# H10R4.net
KiCad netlist of a schematic drawn in EAGLE
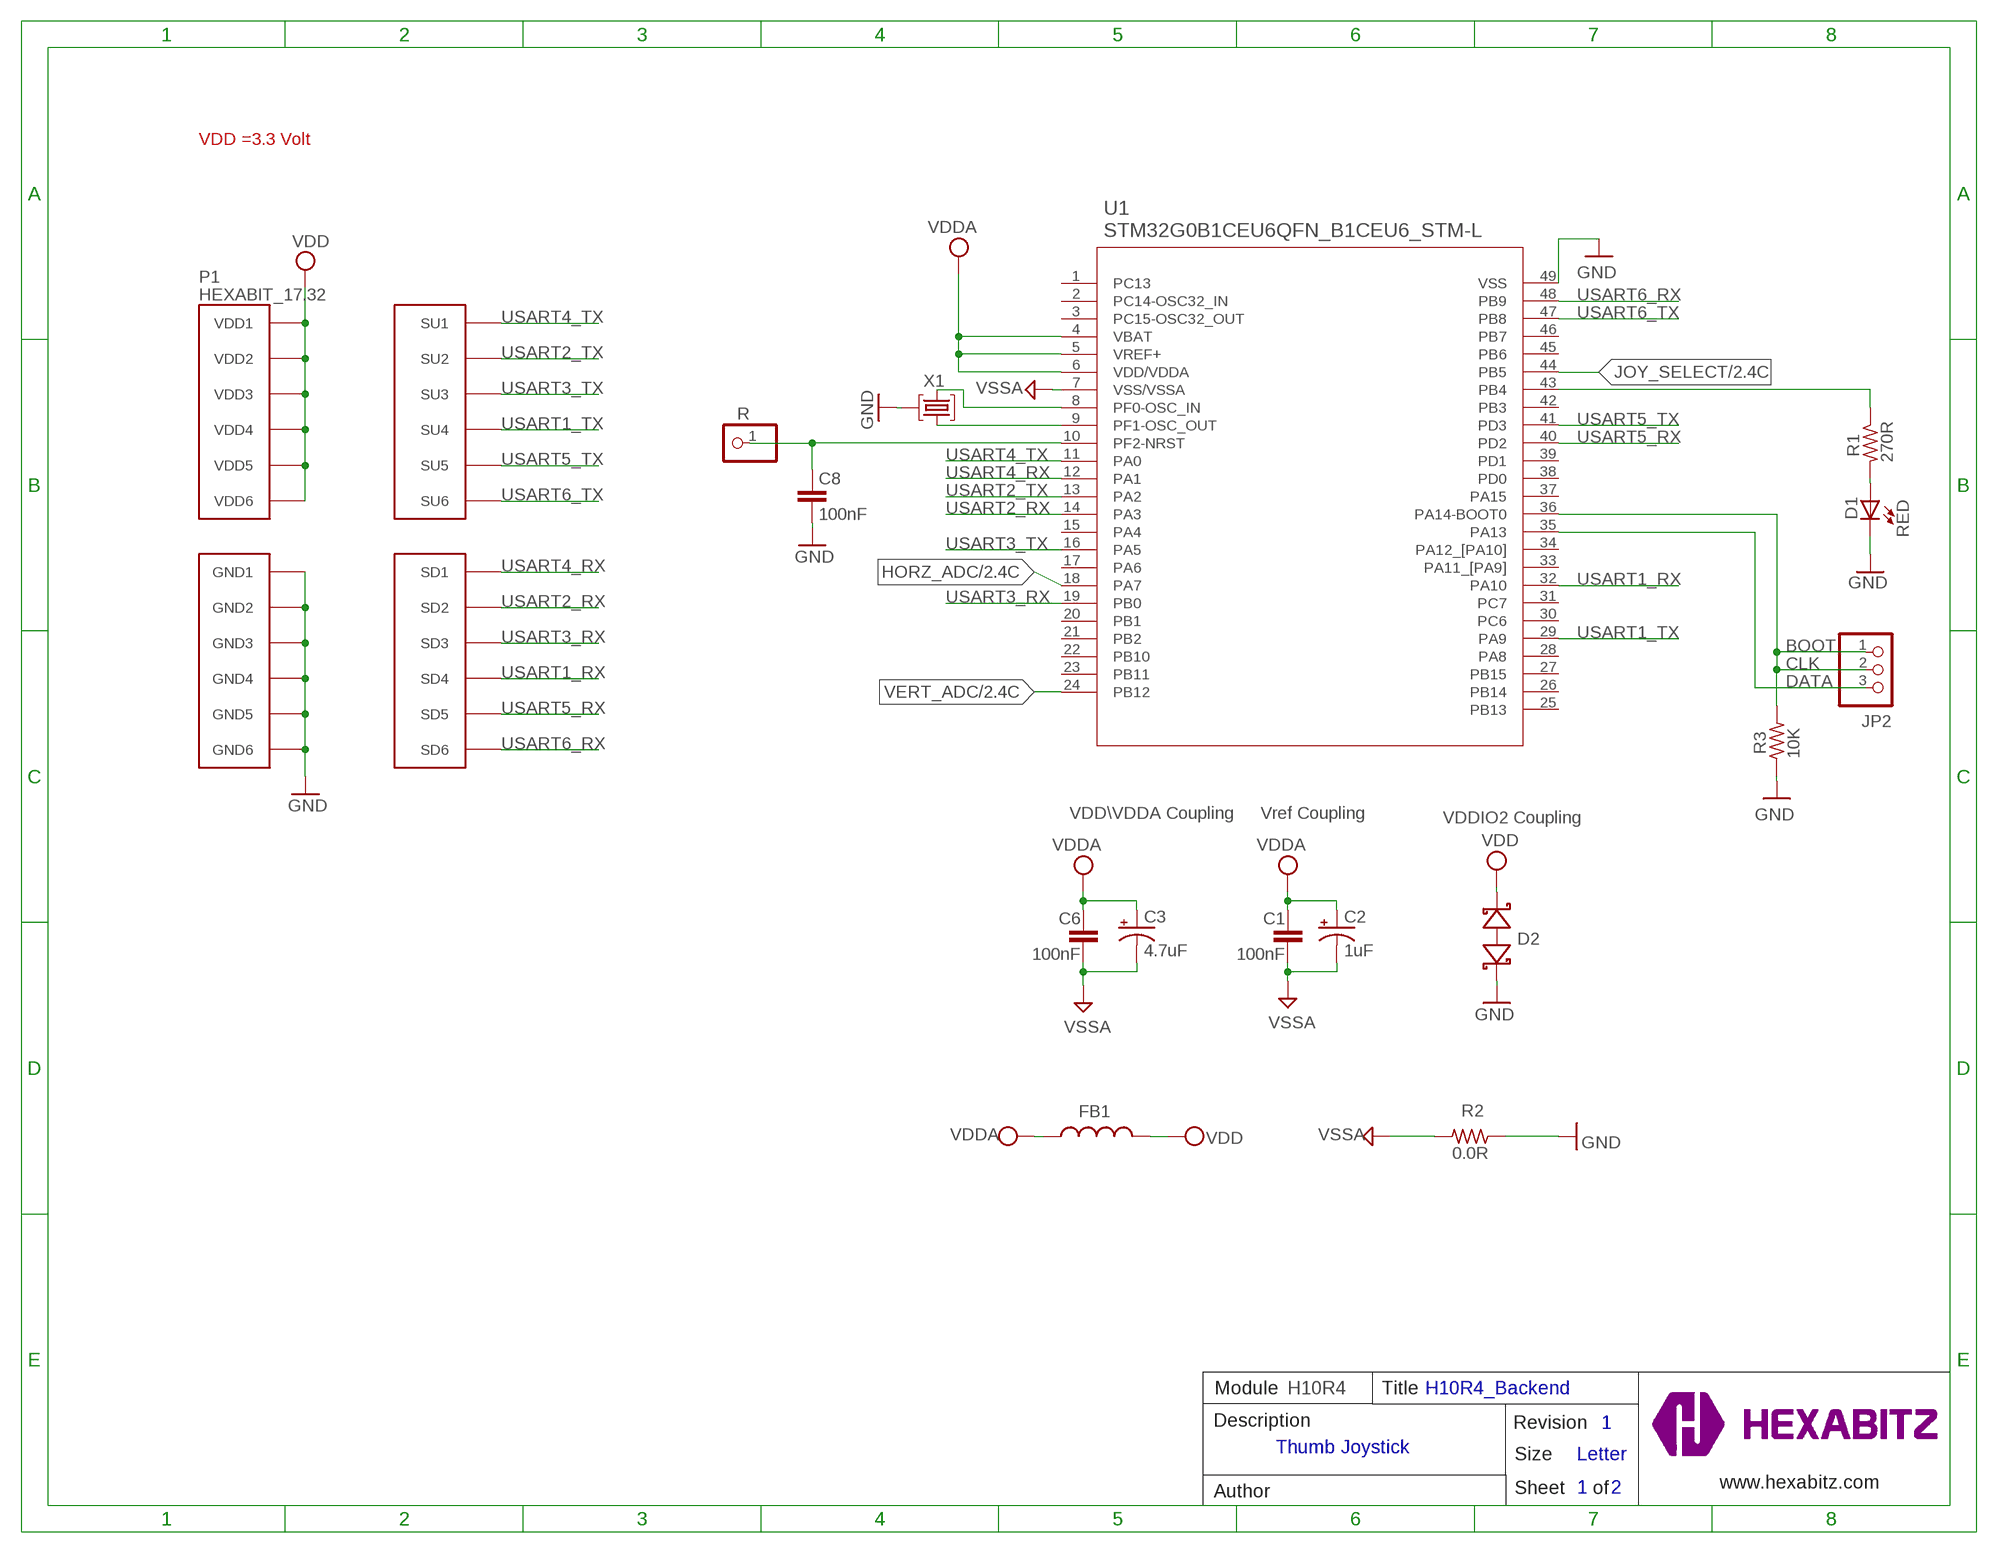
[diagram p0: schematic, sheet 1]
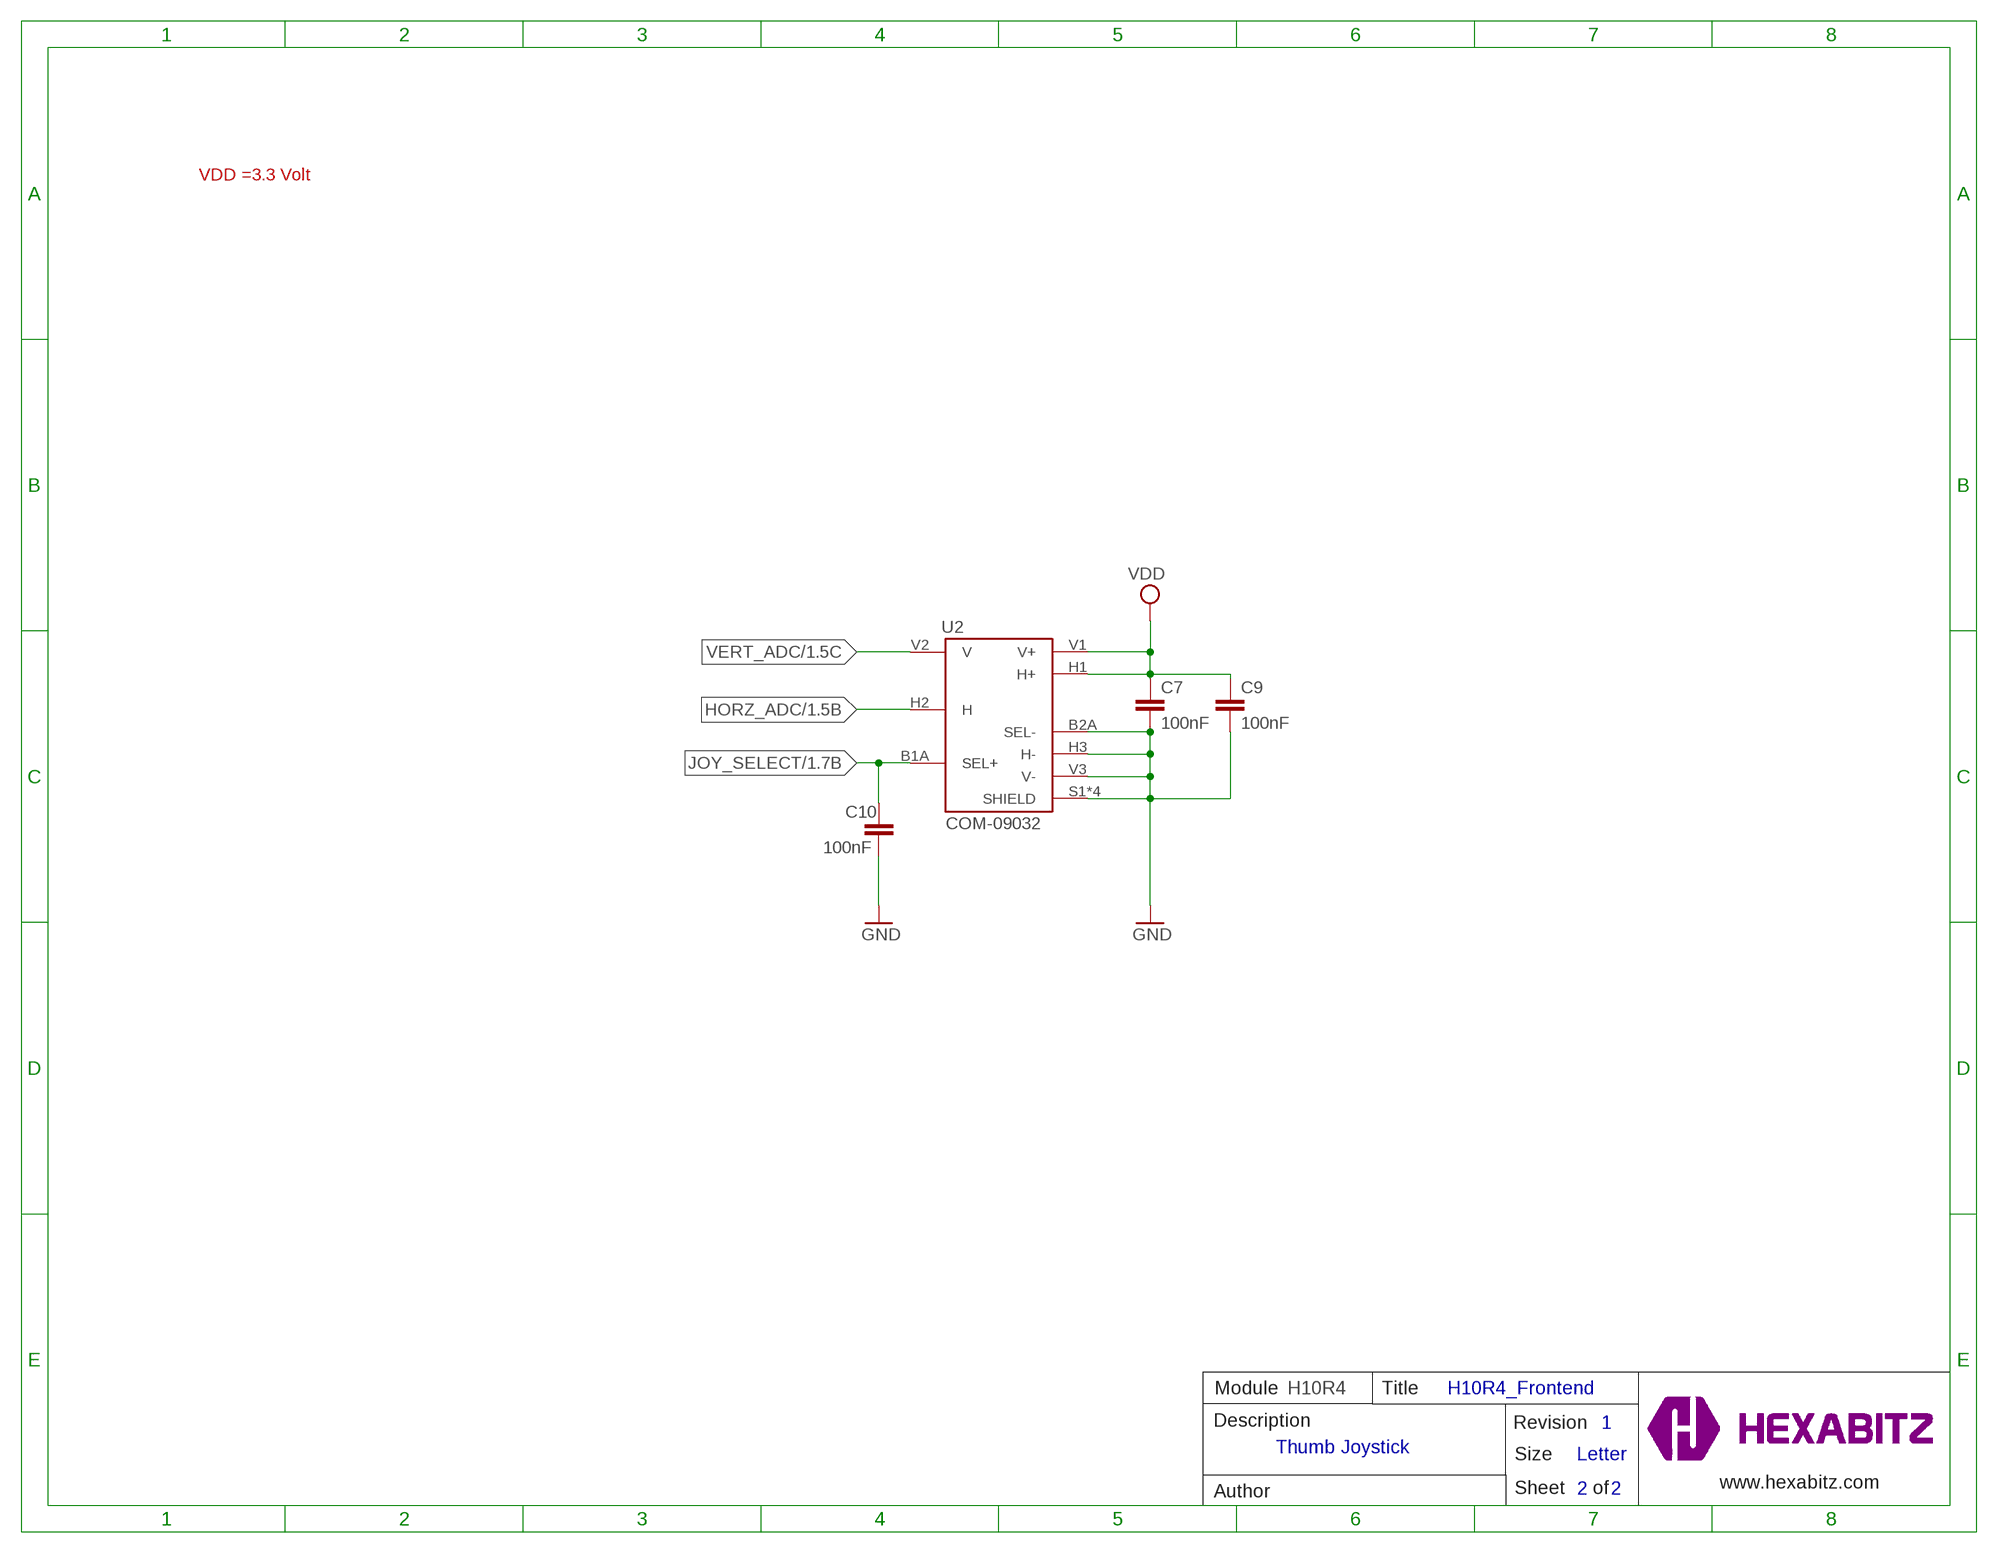
[diagram p1: schematic, sheet 2]

(export (version "E")
  (design (tool "Eeschema 10.0.6"))
  (components
    (comp (ref "C1")
      (value "100nF")
      (footprint "eagle-import:C-0603")
      (libsource (lib "eagle-import") (part "C-0603"))
    )
    (comp (ref "C2")
      (value "1uF")
      (footprint "eagle-import:C-0805-POL")
      (libsource (lib "eagle-import") (part "C-0805-POL"))
    )
    (comp (ref "C3")
      (value "4.7uF")
      (footprint "eagle-import:C-0805-POL")
      (libsource (lib "eagle-import") (part "C-0805-POL"))
    )
    (comp (ref "C6")
      (value "100nF")
      (footprint "eagle-import:C-0603")
      (libsource (lib "eagle-import") (part "C-0603"))
    )
    (comp (ref "C8")
      (value "100nF")
      (footprint "eagle-import:C-0603")
      (libsource (lib "eagle-import") (part "C-0603"))
    )
    (comp (ref "D1")
      (value "RED")
      (footprint "eagle-import:VLMS1300-GS08")
      (fields
        (field (name "MPN") "VLMS1300-GS08")
        (field (name "MFN") "Vishay")
        (field (name "MPN_1") "VLMS1300-GS08")
        (field (name "OCTOPART_URL") "https://octopart.com/vlms1300-gs08-vishay-21709201?r=sp&s=_gcP4_q8T1SC6PJQPTQ9yA")
      )
      (libsource (lib "eagle-import") (part "VLMS1300-GS08"))
    )
    (comp (ref "D2")
      (value "BOURNS_CDSOD323-T03SCBOURNS_CDSOD323-T03SC_0_0")
      (footprint "eagle-import:BOURNS_CDSOD323-T03SC_0")
      (fields (field (name "MPN") "CDSOD323-T03SC"))
      (libsource (lib "eagle-import") (part "BOURNS_CDSOD323-T03SCBOURNS_CDSOD323-T03SC_0_0"))
    )
    (comp (ref "FB1")
      (value "FB-TDK_MMZ1608Y300B")
      (footprint "eagle-import:FB-TDK_MMZ1608Y300B")
      (fields
        (field (name "MFN") "TDK ")
        (field (name "MPN") "MMZ1608Y300B")
        (field (name "OCTOPART_URL") "https://octopart.com/mmz1608y300b-tdk-368280?r=sp&s=cd9_2ZEqQ9q9UNBuQgHAiA")
      )
      (libsource (lib "eagle-import") (part "FB-TDK_MMZ1608Y300B"))
    )
    (comp (ref "JP2")
      (value "PINHD-1X3")
      (footprint "eagle-import:1X03")
      (libsource (lib "eagle-import") (part "PINHD-1X3"))
    )
    (comp (ref "P1")
      (value "HEXABIT_17.32")
      (footprint "eagle-import:HEXABIT_17.32")
      (libsource (lib "eagle-import") (part "HEXABIT_?17.32"))
    )
    (comp (ref "R")
      (value "R")
      (footprint "eagle-import:1X01")
      (fields (field (name "MPN") "87227-1"))
      (libsource (lib "eagle-import") (part "PINHD-1X1"))
    )
    (comp (ref "R1")
      (value "270R")
      (footprint "eagle-import:R-0603")
      (libsource (lib "eagle-import") (part "R-0603"))
    )
    (comp (ref "R2")
      (value "0.0R")
      (footprint "eagle-import:R-0603")
      (fields
        (field (name "MFN") "Yageo")
        (field (name "MPN") "RC0603JR-070RL")
        (field (name "OCTOPART_URL") "https://octopart.com/rc0603jr-070rl-yageo-1241539?r=sp&s=X2NteqRjRNWrnx42Y0aliA")
        (field (name "RESISTANCE") "0.0 Ohm")
      )
      (libsource (lib "eagle-import") (part "R-0603"))
    )
    (comp (ref "R3")
      (value "10K")
      (footprint "eagle-import:R-0603")
      (libsource (lib "eagle-import") (part "R-0603"))
    )
    (comp (ref "TRIMBLE-LOGO1")
      (value "HEXA-LOGO")
      (footprint "eagle-import:HEXA-LOGO")
      (libsource (lib "eagle-import") (part "HEXA-LOGO"))
    )
    (comp (ref "U1")
      (value "STM32G0B1CEU6QFN_B1CEU6_STM-L")
      (footprint "eagle-import:QFN_B1CEU6_STM-L")
      (fields
        (field (name "MANUFACTURER_PART_NUMBER") "STM32G0B1CEU6")
        (field (name "COPYRIGHT") "Copyright (C) 2021 Ultra Librarian. All rights reserved.")
      )
      (libsource (lib "eagle-import") (part "STM32G0B1CEU6QFN_B1CEU6_STM-L"))
    )
    (comp (ref "X1")
      (value "XTALL_CSTCE8M00G52")
      (footprint "eagle-import:XTALL_CSTCE8M00G52")
      (fields (field (name "MPN") "CSTCE8M00G52Z-R0"))
      (libsource (lib "eagle-import") (part "XTALL_CSTCE8M00G52"))
    )
    (comp (ref "C7")
      (value "100nF")
      (footprint "eagle-import:C-0603")
      (fields
        (field (name "CAPACITANCE") "100nF")
        (field (name "MFN") "KEMET")
        (field (name "MPN") "C0603C104K8RACTU")
        (field (name "OCTOPART_URL") "https://octopart.com/c0603c104k8ractu-kemet-145075?r=sp&s=9bS9ASSwSEqMCE9KBEQZ0g")
        (field (name "TOLERANCE") "10%")
        (field (name "VOLTAGE_RATING") "10V")
      )
      (libsource (lib "eagle-import") (part "C-0603"))
    )
    (comp (ref "C9")
      (value "100nF")
      (footprint "eagle-import:C-0603")
      (libsource (lib "eagle-import") (part "C-0603"))
    )
    (comp (ref "C10")
      (value "100nF")
      (footprint "eagle-import:C-0603")
      (fields
        (field (name "CAPACITANCE") "100nF")
        (field (name "MFN") "KEMET")
        (field (name "MPN") "C0603C104K8RACTU")
        (field (name "OCTOPART_URL") "https://octopart.com/c0603c104k8ractu-kemet-145075?r=sp&s=9bS9ASSwSEqMCE9KBEQZ0g")
        (field (name "TOLERANCE") "10%")
        (field (name "VOLTAGE_RATING") "10V")
      )
      (libsource (lib "eagle-import") (part "C-0603"))
    )
    (comp (ref "U2")
      (value "COM-09032")
      (footprint "eagle-import:XDCR_COM-09032")
      (fields (field (name "MF") "SparkFun Electronics"))
      (libsource (lib "eagle-import") (part "COM-09032"))
    )
  )
  (nets
    (net (code "1") (name "CLK") (class "Default")
      (node (ref "JP2") (pin "1") (pinfunction "1_1") (pintype "passive"))
      (node (ref "JP2") (pin "2") (pinfunction "2_2") (pintype "passive"))
      (node (ref "R3") (pin "2") (pinfunction "2_2") (pintype "passive"))
      (node (ref "U1") (pin "36") (pinfunction "PA14-BOOT0_36") (pintype "bidirectional"))
    )
    (net (code "2") (name "DATA") (class "Default")
      (node (ref "JP2") (pin "3") (pinfunction "3_3") (pintype "passive"))
      (node (ref "U1") (pin "35") (pinfunction "PA13_35") (pintype "bidirectional"))
    )
    (net (code "3") (name "GND") (class "Default")
      (node (ref "C10") (pin "2") (pinfunction "2_2") (pintype "passive"))
      (node (ref "C7") (pin "2") (pinfunction "2_2") (pintype "passive"))
      (node (ref "C8") (pin "2") (pinfunction "2_2") (pintype "passive"))
      (node (ref "C9") (pin "2") (pinfunction "2_2") (pintype "passive"))
      (node (ref "D1") (pin "C") (pinfunction "C_C") (pintype "passive"))
      (node (ref "D2") (pin "1") (pinfunction "A_1") (pintype "passive"))
      (node (ref "P1") (pin "PAD_PD10") (pinfunction "GND4_PAD_PD10") (pintype "power_in"))
      (node (ref "P1") (pin "PAD_PD11") (pinfunction "GND5_PAD_PD11") (pintype "power_in"))
      (node (ref "P1") (pin "PAD_PD12") (pinfunction "GND6_PAD_PD12") (pintype "power_in"))
      (node (ref "P1") (pin "PAD_PD7") (pinfunction "GND1_PAD_PD7") (pintype "power_in"))
      (node (ref "P1") (pin "PAD_PD8") (pinfunction "GND2_PAD_PD8") (pintype "power_in"))
      (node (ref "P1") (pin "PAD_PD9") (pinfunction "GND3_PAD_PD9") (pintype "power_in"))
      (node (ref "R2") (pin "1") (pinfunction "1_1") (pintype "passive"))
      (node (ref "R3") (pin "1") (pinfunction "1_1") (pintype "passive"))
      (node (ref "U1") (pin "49") (pinfunction "VSS_49") (pintype "passive"))
      (node (ref "U2") (pin "B2A") (pinfunction "SEL-_B2A") (pintype "passive"))
      (node (ref "U2") (pin "H3") (pinfunction "H-_H3") (pintype "passive"))
      (node (ref "U2") (pin "S1") (pinfunction "SHIELD_S1") (pintype "passive"))
      (node (ref "U2") (pin "S2") (pinfunction "SHIELD_S2") (pintype "passive"))
      (node (ref "U2") (pin "S3") (pinfunction "SHIELD_S3") (pintype "passive"))
      (node (ref "U2") (pin "S4") (pinfunction "SHIELD_S4") (pintype "passive"))
      (node (ref "U2") (pin "V3") (pinfunction "V-_V3") (pintype "passive"))
      (node (ref "X1") (pin "P$2") (pinfunction "2_P$2") (pintype "passive"))
    )
    (net (code "4") (name "HORZ_ADC") (class "Default")
      (node (ref "U1") (pin "18") (pinfunction "PA7_18") (pintype "bidirectional"))
      (node (ref "U2") (pin "H2") (pinfunction "H_H2") (pintype "passive"))
    )
    (net (code "5") (name "JOY_SELECT") (class "Default")
      (node (ref "C10") (pin "1") (pinfunction "1_1") (pintype "passive"))
      (node (ref "U1") (pin "44") (pinfunction "PB5_44") (pintype "bidirectional"))
      (node (ref "U2") (pin "B1A") (pinfunction "SEL+_B1A") (pintype "passive"))
    )
    (net (code "6") (name "Net-(D1-PadA)") (class "Default")
      (node (ref "D1") (pin "A") (pinfunction "A_A") (pintype "passive"))
      (node (ref "R1") (pin "2") (pinfunction "2_2") (pintype "passive"))
    )
    (net (code "7") (name "Net-(U1-PB4)") (class "Default")
      (node (ref "R1") (pin "1") (pinfunction "1_1") (pintype "passive"))
      (node (ref "U1") (pin "43") (pinfunction "PB4_43") (pintype "bidirectional"))
    )
    (net (code "8") (name "Net-(U1-PF0-OSC_IN)") (class "Default")
      (node (ref "U1") (pin "8") (pinfunction "PF0-OSC_IN_8") (pintype "bidirectional"))
      (node (ref "X1") (pin "P$3") (pinfunction "3_P$3") (pintype "passive"))
    )
    (net (code "9") (name "Net-(U1-PF1-OSC_OUT)") (class "Default")
      (node (ref "U1") (pin "9") (pinfunction "PF1-OSC_OUT_9") (pintype "output"))
      (node (ref "X1") (pin "P$1") (pinfunction "1_P$1") (pintype "passive"))
    )
    (net (code "10") (name "Net-(U1-PF2-NRST)") (class "Default")
      (node (ref "C8") (pin "1") (pinfunction "1_1") (pintype "passive"))
      (node (ref "R") (pin "1") (pinfunction "1_1") (pintype "passive"))
      (node (ref "U1") (pin "10") (pinfunction "PF2-NRST_10") (pintype "bidirectional"))
    )
    (net (code "11") (name "USART1_RX") (class "Default")
      (node (ref "P1") (pin "PAD_PD4") (pinfunction "SD4_PAD_PD4") (pintype "bidirectional"))
      (node (ref "U1") (pin "32") (pinfunction "PA10_32") (pintype "bidirectional"))
    )
    (net (code "12") (name "USART1_TX") (class "Default")
      (node (ref "P1") (pin "PAD_PU4") (pinfunction "SU4_PAD_PU4") (pintype "bidirectional"))
      (node (ref "U1") (pin "29") (pinfunction "PA9_29") (pintype "bidirectional"))
    )
    (net (code "13") (name "USART2_RX") (class "Default")
      (node (ref "P1") (pin "PAD_PD2") (pinfunction "SD2_PAD_PD2") (pintype "bidirectional"))
      (node (ref "U1") (pin "14") (pinfunction "PA3_14") (pintype "bidirectional"))
    )
    (net (code "14") (name "USART2_TX") (class "Default")
      (node (ref "P1") (pin "PAD_PU2") (pinfunction "SU2_PAD_PU2") (pintype "bidirectional"))
      (node (ref "U1") (pin "13") (pinfunction "PA2_13") (pintype "bidirectional"))
    )
    (net (code "15") (name "USART3_RX") (class "Default")
      (node (ref "P1") (pin "PAD_PD3") (pinfunction "SD3_PAD_PD3") (pintype "bidirectional"))
      (node (ref "U1") (pin "19") (pinfunction "PB0_19") (pintype "bidirectional"))
    )
    (net (code "16") (name "USART3_TX") (class "Default")
      (node (ref "P1") (pin "PAD_PU3") (pinfunction "SU3_PAD_PU3") (pintype "bidirectional"))
      (node (ref "U1") (pin "16") (pinfunction "PA5_16") (pintype "bidirectional"))
    )
    (net (code "17") (name "USART4_RX") (class "Default")
      (node (ref "P1") (pin "PAD_PD1") (pinfunction "SD1_PAD_PD1") (pintype "bidirectional"))
      (node (ref "U1") (pin "12") (pinfunction "PA1_12") (pintype "bidirectional"))
    )
    (net (code "18") (name "USART4_TX") (class "Default")
      (node (ref "P1") (pin "PAD_PU1") (pinfunction "SU1_PAD_PU1") (pintype "bidirectional"))
      (node (ref "U1") (pin "11") (pinfunction "PA0_11") (pintype "bidirectional"))
    )
    (net (code "19") (name "USART5_RX") (class "Default")
      (node (ref "P1") (pin "PAD_PD5") (pinfunction "SD5_PAD_PD5") (pintype "bidirectional"))
      (node (ref "U1") (pin "40") (pinfunction "PD2_40") (pintype "bidirectional"))
    )
    (net (code "20") (name "USART5_TX") (class "Default")
      (node (ref "P1") (pin "PAD_PU5") (pinfunction "SU5_PAD_PU5") (pintype "bidirectional"))
      (node (ref "U1") (pin "41") (pinfunction "PD3_41") (pintype "bidirectional"))
    )
    (net (code "21") (name "USART6_RX") (class "Default")
      (node (ref "P1") (pin "PAD_PD6") (pinfunction "SD6_PAD_PD6") (pintype "bidirectional"))
      (node (ref "U1") (pin "48") (pinfunction "PB9_48") (pintype "bidirectional"))
    )
    (net (code "22") (name "USART6_TX") (class "Default")
      (node (ref "P1") (pin "PAD_PU6") (pinfunction "SU6_PAD_PU6") (pintype "bidirectional"))
      (node (ref "U1") (pin "47") (pinfunction "PB8_47") (pintype "bidirectional"))
    )
    (net (code "23") (name "VDD") (class "Default")
      (node (ref "C7") (pin "1") (pinfunction "1_1") (pintype "passive"))
      (node (ref "C9") (pin "1") (pinfunction "1_1") (pintype "passive"))
      (node (ref "D2") (pin "2") (pinfunction "C_2") (pintype "passive"))
      (node (ref "FB1") (pin "2") (pinfunction "2_2") (pintype "passive"))
      (node (ref "P1") (pin "PAD_PU10") (pinfunction "VDD4_PAD_PU10") (pintype "power_in"))
      (node (ref "P1") (pin "PAD_PU11") (pinfunction "VDD5_PAD_PU11") (pintype "power_in"))
      (node (ref "P1") (pin "PAD_PU12") (pinfunction "VDD6_PAD_PU12") (pintype "power_in"))
      (node (ref "P1") (pin "PAD_PU7") (pinfunction "VDD1_PAD_PU7") (pintype "power_in"))
      (node (ref "P1") (pin "PAD_PU8") (pinfunction "VDD2_PAD_PU8") (pintype "power_in"))
      (node (ref "P1") (pin "PAD_PU9") (pinfunction "VDD3_PAD_PU9") (pintype "power_in"))
      (node (ref "U2") (pin "H1") (pinfunction "H+_H1") (pintype "passive"))
      (node (ref "U2") (pin "V1") (pinfunction "V+_V1") (pintype "passive"))
    )
    (net (code "24") (name "VDDA") (class "Default")
      (node (ref "C1") (pin "1") (pinfunction "1_1") (pintype "passive"))
      (node (ref "C2") (pin "1") (pinfunction "+_1") (pintype "passive"))
      (node (ref "C3") (pin "1") (pinfunction "+_1") (pintype "passive"))
      (node (ref "C6") (pin "1") (pinfunction "1_1") (pintype "passive"))
      (node (ref "FB1") (pin "1") (pinfunction "1_1") (pintype "passive"))
      (node (ref "U1") (pin "4") (pinfunction "VBAT_4") (pintype "passive"))
      (node (ref "U1") (pin "5") (pinfunction "VREF+_5") (pintype "power_in"))
      (node (ref "U1") (pin "6") (pinfunction "VDD/VDDA_6") (pintype "power_in"))
    )
    (net (code "25") (name "VERT_ADC") (class "Default")
      (node (ref "U1") (pin "24") (pinfunction "PB12_24") (pintype "bidirectional"))
      (node (ref "U2") (pin "V2") (pinfunction "V_V2") (pintype "passive"))
    )
    (net (code "26") (name "VSSA") (class "Default")
      (node (ref "C1") (pin "2") (pinfunction "2_2") (pintype "passive"))
      (node (ref "C2") (pin "2") (pinfunction "-_2") (pintype "passive"))
      (node (ref "C3") (pin "2") (pinfunction "-_2") (pintype "passive"))
      (node (ref "C6") (pin "2") (pinfunction "2_2") (pintype "passive"))
      (node (ref "R2") (pin "2") (pinfunction "2_2") (pintype "passive"))
      (node (ref "U1") (pin "7") (pinfunction "VSS/VSSA_7") (pintype "passive"))
    )
    (net (code "27") (name "unconnected-(U1-PA4-Pad15)") (class "Default")
      (node (ref "U1") (pin "15") (pinfunction "PA4_15") (pintype "bidirectional"))
    )
    (net (code "28") (name "unconnected-(U1-PA6-Pad17)") (class "Default")
      (node (ref "U1") (pin "17") (pinfunction "PA6_17") (pintype "bidirectional"))
    )
    (net (code "29") (name "unconnected-(U1-PA8-Pad28)") (class "Default")
      (node (ref "U1") (pin "28") (pinfunction "PA8_28") (pintype "bidirectional"))
    )
    (net (code "30") (name "unconnected-(U1-PA11_[PA9]-Pad33)") (class "Default")
      (node (ref "U1") (pin "33") (pinfunction "PA11_[PA9]_33") (pintype "bidirectional"))
    )
    (net (code "31") (name "unconnected-(U1-PA12_[PA10]-Pad34)") (class "Default")
      (node (ref "U1") (pin "34") (pinfunction "PA12_[PA10]_34") (pintype "bidirectional"))
    )
    (net (code "32") (name "unconnected-(U1-PA15-Pad37)") (class "Default")
      (node (ref "U1") (pin "37") (pinfunction "PA15_37") (pintype "bidirectional"))
    )
    (net (code "33") (name "unconnected-(U1-PB1-Pad20)") (class "Default")
      (node (ref "U1") (pin "20") (pinfunction "PB1_20") (pintype "bidirectional"))
    )
    (net (code "34") (name "unconnected-(U1-PB2-Pad21)") (class "Default")
      (node (ref "U1") (pin "21") (pinfunction "PB2_21") (pintype "bidirectional"))
    )
    (net (code "35") (name "unconnected-(U1-PB3-Pad42)") (class "Default")
      (node (ref "U1") (pin "42") (pinfunction "PB3_42") (pintype "bidirectional"))
    )
    (net (code "36") (name "unconnected-(U1-PB6-Pad45)") (class "Default")
      (node (ref "U1") (pin "45") (pinfunction "PB6_45") (pintype "bidirectional"))
    )
    (net (code "37") (name "unconnected-(U1-PB7-Pad46)") (class "Default")
      (node (ref "U1") (pin "46") (pinfunction "PB7_46") (pintype "bidirectional"))
    )
    (net (code "38") (name "unconnected-(U1-PB10-Pad22)") (class "Default")
      (node (ref "U1") (pin "22") (pinfunction "PB10_22") (pintype "bidirectional"))
    )
    (net (code "39") (name "unconnected-(U1-PB11-Pad23)") (class "Default")
      (node (ref "U1") (pin "23") (pinfunction "PB11_23") (pintype "bidirectional"))
    )
    (net (code "40") (name "unconnected-(U1-PB13-Pad25)") (class "Default")
      (node (ref "U1") (pin "25") (pinfunction "PB13_25") (pintype "bidirectional"))
    )
    (net (code "41") (name "unconnected-(U1-PB14-Pad26)") (class "Default")
      (node (ref "U1") (pin "26") (pinfunction "PB14_26") (pintype "bidirectional"))
    )
    (net (code "42") (name "unconnected-(U1-PB15-Pad27)") (class "Default")
      (node (ref "U1") (pin "27") (pinfunction "PB15_27") (pintype "bidirectional"))
    )
    (net (code "43") (name "unconnected-(U1-PC6-Pad30)") (class "Default")
      (node (ref "U1") (pin "30") (pinfunction "PC6_30") (pintype "bidirectional"))
    )
    (net (code "44") (name "unconnected-(U1-PC7-Pad31)") (class "Default")
      (node (ref "U1") (pin "31") (pinfunction "PC7_31") (pintype "bidirectional"))
    )
    (net (code "45") (name "unconnected-(U1-PC13-Pad1)") (class "Default")
      (node (ref "U1") (pin "1") (pinfunction "PC13_1") (pintype "bidirectional"))
    )
    (net (code "46") (name "unconnected-(U1-PC14-OSC32_IN-Pad2)") (class "Default")
      (node (ref "U1") (pin "2") (pinfunction "PC14-OSC32_IN_2") (pintype "bidirectional"))
    )
    (net (code "47") (name "unconnected-(U1-PC15-OSC32_OUT-Pad3)") (class "Default")
      (node (ref "U1") (pin "3") (pinfunction "PC15-OSC32_OUT_3") (pintype "output"))
    )
    (net (code "48") (name "unconnected-(U1-PD0-Pad38)") (class "Default")
      (node (ref "U1") (pin "38") (pinfunction "PD0_38") (pintype "bidirectional"))
    )
    (net (code "49") (name "unconnected-(U1-PD1-Pad39)") (class "Default")
      (node (ref "U1") (pin "39") (pinfunction "PD1_39") (pintype "bidirectional"))
    )
  )
)
